# MSP430G2553_H-Bridge_Servo_Sensors_Inter.net
KiCad netlist of a schematic drawn in EAGLE
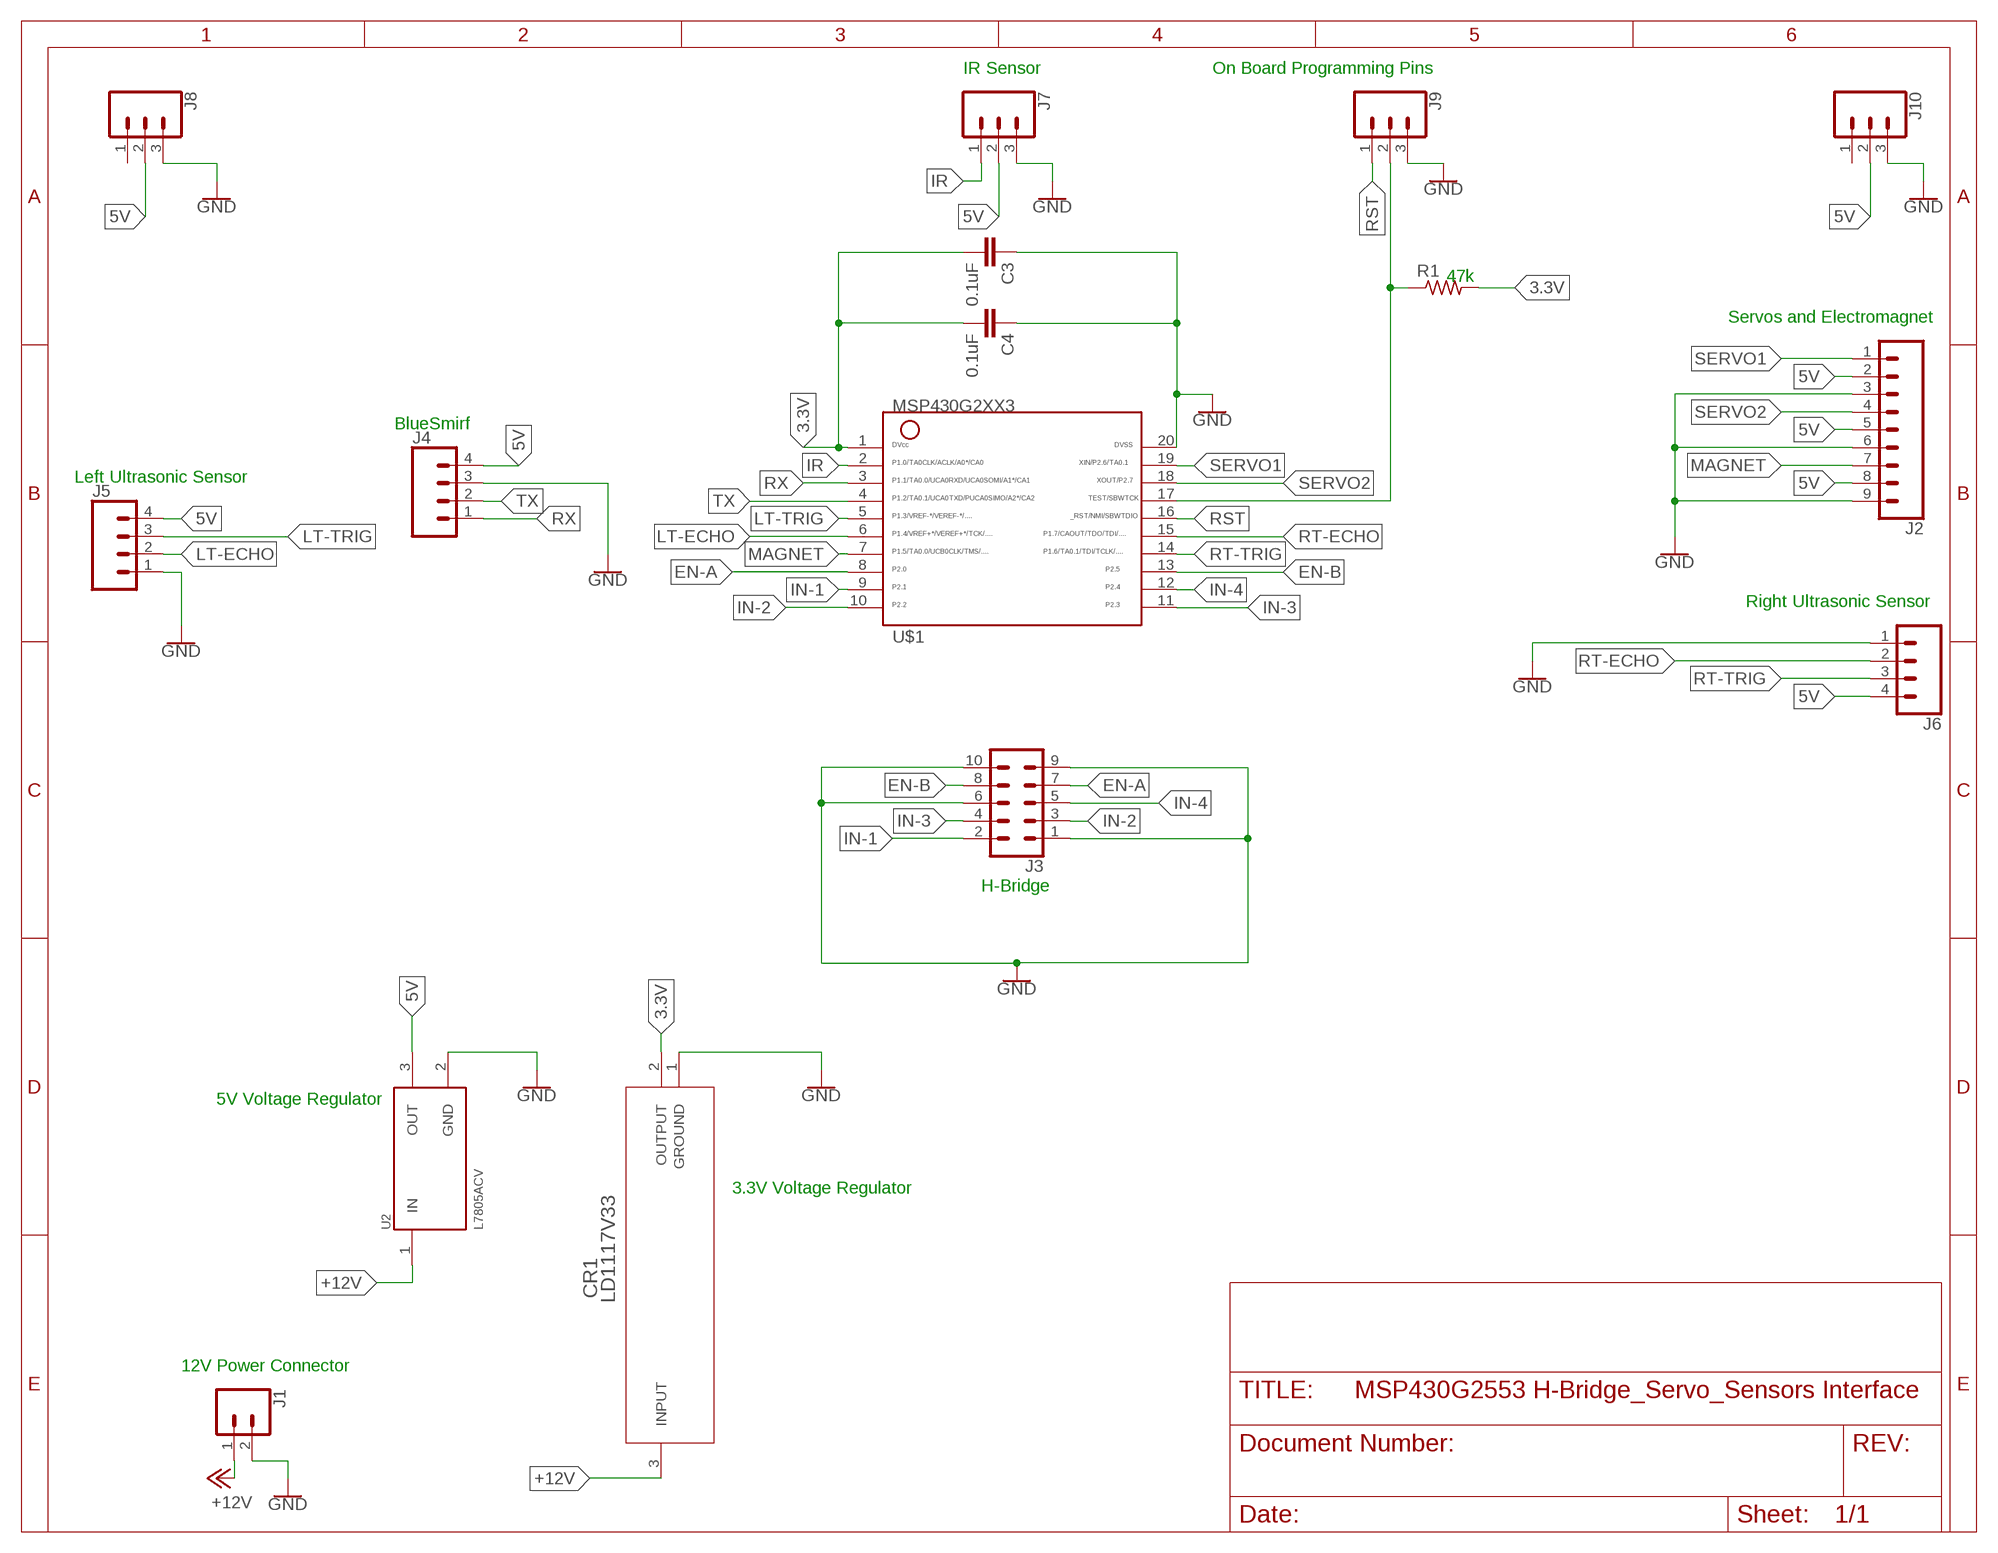
[diagram p0: schematic, sheet 1]

(export (version "E")
  (design (tool "Eeschema 10.0.6"))
  (components
    (comp (ref "C3")
      (value "0.1uF")
      (footprint "eagle-import:0402")
      (libsource (lib "eagle-import") (part "0.1UF-0402-16V-10%"))
    )
    (comp (ref "C4")
      (value "0.1uF")
      (footprint "eagle-import:0402")
      (libsource (lib "eagle-import") (part "0.1UF-0402-16V-10%"))
    )
    (comp (ref "CR1")
      (value "LD1117V33")
      (footprint "eagle-import:TO-220")
      (libsource (lib "eagle-import") (part "LD1117V33"))
    )
    (comp (ref "J1")
      (value "CONN_023.5MM")
      (footprint "eagle-import:SCREWTERMINAL-3.5MM-2")
      (libsource (lib "eagle-import") (part "CONN_023.5MM"))
    )
    (comp (ref "J2")
      (value "CONN_09")
      (footprint "eagle-import:1X09")
      (libsource (lib "eagle-import") (part "CONN_09"))
    )
    (comp (ref "J3")
      (value "CONN_05X2PTH")
      (footprint "eagle-import:2X5")
      (libsource (lib "eagle-import") (part "CONN_05X2PTH"))
    )
    (comp (ref "J4")
      (value "CONN_04")
      (footprint "eagle-import:1X04")
      (libsource (lib "eagle-import") (part "CONN_04"))
    )
    (comp (ref "J5")
      (value "CONN_04")
      (footprint "eagle-import:1X04")
      (libsource (lib "eagle-import") (part "CONN_04"))
    )
    (comp (ref "J6")
      (value "CONN_04")
      (footprint "eagle-import:1X04")
      (libsource (lib "eagle-import") (part "CONN_04"))
    )
    (comp (ref "J7")
      (value "CONN_03")
      (footprint "eagle-import:1X03")
      (libsource (lib "eagle-import") (part "CONN_03"))
    )
    (comp (ref "J8")
      (value "CONN_03")
      (footprint "eagle-import:1X03")
      (libsource (lib "eagle-import") (part "CONN_03"))
    )
    (comp (ref "J9")
      (value "CONN_03")
      (footprint "eagle-import:1X03")
      (libsource (lib "eagle-import") (part "CONN_03"))
    )
    (comp (ref "J10")
      (value "CONN_03")
      (footprint "eagle-import:1X03")
      (libsource (lib "eagle-import") (part "CONN_03"))
    )
    (comp (ref "R1")
      (value "R-US_R0201")
      (footprint "eagle-import:R0201")
      (libsource (lib "eagle-import") (part "R-US_R0201"))
    )
    (comp (ref "U$1")
      (value "G2XX3---N20")
      (footprint "eagle-import:N20")
      (libsource (lib "eagle-import") (part "G2XX3---N20"))
    )
    (comp (ref "U2")
      (value "L7805ACV")
      (footprint "eagle-import:TO254P460X1020X1945-3P")
      (fields (field (name "DIGI-KEY_PART_NUMBER") "497-1441-5-ND") (field (name "MF") "STMicroelectronics"))
      (libsource (lib "eagle-import") (part "L7805ACV"))
    )
  )
  (nets
    (net (code "1") (name "+12V") (class "Default")
      (node (ref "CR1") (pin "3") (pinfunction "INPUT_3") (pintype "passive"))
      (node (ref "J1") (pin "1") (pinfunction "1_1") (pintype "passive"))
      (node (ref "U2") (pin "1") (pinfunction "IN_1") (pintype "input"))
    )
    (net (code "2") (name "3.3V") (class "Default")
      (node (ref "C3") (pin "2") (pinfunction "2_2") (pintype "passive"))
      (node (ref "C4") (pin "2") (pinfunction "2_2") (pintype "passive"))
      (node (ref "CR1") (pin "2") (pinfunction "OUTPUT_2") (pintype "passive"))
      (node (ref "R1") (pin "2") (pinfunction "2_2") (pintype "passive"))
      (node (ref "U$1") (pin "1") (pinfunction "1_1") (pintype "bidirectional"))
    )
    (net (code "3") (name "5V") (class "Default")
      (node (ref "J10") (pin "2") (pinfunction "2_2") (pintype "passive"))
      (node (ref "J2") (pin "2") (pinfunction "2_2") (pintype "passive"))
      (node (ref "J2") (pin "5") (pinfunction "5_5") (pintype "passive"))
      (node (ref "J2") (pin "8") (pinfunction "8_8") (pintype "passive"))
      (node (ref "J4") (pin "4") (pinfunction "4_4") (pintype "passive"))
      (node (ref "J5") (pin "4") (pinfunction "4_4") (pintype "passive"))
      (node (ref "J6") (pin "4") (pinfunction "4_4") (pintype "passive"))
      (node (ref "J7") (pin "2") (pinfunction "2_2") (pintype "passive"))
      (node (ref "J8") (pin "2") (pinfunction "2_2") (pintype "passive"))
      (node (ref "U2") (pin "3") (pinfunction "OUT_3") (pintype "output"))
    )
    (net (code "4") (name "EN-A") (class "Default")
      (node (ref "J3") (pin "7") (pinfunction "7_7") (pintype "passive"))
      (node (ref "U$1") (pin "8") (pinfunction "8_8") (pintype "bidirectional"))
    )
    (net (code "5") (name "EN-B") (class "Default")
      (node (ref "J3") (pin "8") (pinfunction "8_8") (pintype "passive"))
      (node (ref "U$1") (pin "13") (pinfunction "13_13") (pintype "bidirectional"))
    )
    (net (code "6") (name "GND") (class "Default")
      (node (ref "C3") (pin "1") (pinfunction "1_1") (pintype "passive"))
      (node (ref "C4") (pin "1") (pinfunction "1_1") (pintype "passive"))
      (node (ref "CR1") (pin "1") (pinfunction "GROUND_1") (pintype "passive"))
      (node (ref "J1") (pin "2") (pinfunction "2_2") (pintype "passive"))
      (node (ref "J10") (pin "3") (pinfunction "3_3") (pintype "passive"))
      (node (ref "J2") (pin "3") (pinfunction "3_3") (pintype "passive"))
      (node (ref "J2") (pin "6") (pinfunction "6_6") (pintype "passive"))
      (node (ref "J2") (pin "9") (pinfunction "9_9") (pintype "passive"))
      (node (ref "J3") (pin "1") (pinfunction "1_1") (pintype "passive"))
      (node (ref "J3") (pin "10") (pinfunction "10_10") (pintype "passive"))
      (node (ref "J3") (pin "6") (pinfunction "6_6") (pintype "passive"))
      (node (ref "J3") (pin "9") (pinfunction "9_9") (pintype "passive"))
      (node (ref "J4") (pin "3") (pinfunction "3_3") (pintype "passive"))
      (node (ref "J5") (pin "1") (pinfunction "1_1") (pintype "passive"))
      (node (ref "J6") (pin "1") (pinfunction "1_1") (pintype "passive"))
      (node (ref "J7") (pin "3") (pinfunction "3_3") (pintype "passive"))
      (node (ref "J8") (pin "3") (pinfunction "3_3") (pintype "passive"))
      (node (ref "J9") (pin "3") (pinfunction "3_3") (pintype "passive"))
      (node (ref "U$1") (pin "20") (pinfunction "20_20") (pintype "bidirectional"))
      (node (ref "U2") (pin "2") (pinfunction "GND_2") (pintype "power_in"))
    )
    (net (code "7") (name "IN-1") (class "Default")
      (node (ref "J3") (pin "2") (pinfunction "2_2") (pintype "passive"))
      (node (ref "U$1") (pin "9") (pinfunction "9_9") (pintype "bidirectional"))
    )
    (net (code "8") (name "IN-2") (class "Default")
      (node (ref "J3") (pin "3") (pinfunction "3_3") (pintype "passive"))
      (node (ref "U$1") (pin "10") (pinfunction "10_10") (pintype "bidirectional"))
    )
    (net (code "9") (name "IN-3") (class "Default")
      (node (ref "J3") (pin "4") (pinfunction "4_4") (pintype "passive"))
      (node (ref "U$1") (pin "11") (pinfunction "11_11") (pintype "bidirectional"))
    )
    (net (code "10") (name "IN-4") (class "Default")
      (node (ref "J3") (pin "5") (pinfunction "5_5") (pintype "passive"))
      (node (ref "U$1") (pin "12") (pinfunction "12_12") (pintype "bidirectional"))
    )
    (net (code "11") (name "IR") (class "Default")
      (node (ref "J7") (pin "1") (pinfunction "1_1") (pintype "passive"))
      (node (ref "U$1") (pin "2") (pinfunction "2_2") (pintype "bidirectional"))
    )
    (net (code "12") (name "LT-ECHO") (class "Default")
      (node (ref "J5") (pin "2") (pinfunction "2_2") (pintype "passive"))
      (node (ref "U$1") (pin "6") (pinfunction "6_6") (pintype "bidirectional"))
    )
    (net (code "13") (name "LT-TRIG") (class "Default")
      (node (ref "J5") (pin "3") (pinfunction "3_3") (pintype "passive"))
      (node (ref "U$1") (pin "5") (pinfunction "5_5") (pintype "bidirectional"))
    )
    (net (code "14") (name "MAGNET") (class "Default")
      (node (ref "J2") (pin "7") (pinfunction "7_7") (pintype "passive"))
      (node (ref "U$1") (pin "7") (pinfunction "7_7") (pintype "bidirectional"))
    )
    (net (code "15") (name "Net-(J9-Pad2)") (class "Default")
      (node (ref "J9") (pin "2") (pinfunction "2_2") (pintype "passive"))
      (node (ref "R1") (pin "1") (pinfunction "1_1") (pintype "passive"))
      (node (ref "U$1") (pin "17") (pinfunction "17_17") (pintype "bidirectional"))
    )
    (net (code "16") (name "RST") (class "Default")
      (node (ref "J9") (pin "1") (pinfunction "1_1") (pintype "passive"))
      (node (ref "U$1") (pin "16") (pinfunction "16_16") (pintype "bidirectional"))
    )
    (net (code "17") (name "RT-ECHO") (class "Default")
      (node (ref "J6") (pin "2") (pinfunction "2_2") (pintype "passive"))
      (node (ref "U$1") (pin "15") (pinfunction "15_15") (pintype "bidirectional"))
    )
    (net (code "18") (name "RT-TRIG") (class "Default")
      (node (ref "J6") (pin "3") (pinfunction "3_3") (pintype "passive"))
      (node (ref "U$1") (pin "14") (pinfunction "14_14") (pintype "bidirectional"))
    )
    (net (code "19") (name "RX") (class "Default")
      (node (ref "J4") (pin "1") (pinfunction "1_1") (pintype "passive"))
      (node (ref "U$1") (pin "3") (pinfunction "3_3") (pintype "bidirectional"))
    )
    (net (code "20") (name "SERVO1") (class "Default")
      (node (ref "J2") (pin "1") (pinfunction "1_1") (pintype "passive"))
      (node (ref "U$1") (pin "19") (pinfunction "19_19") (pintype "bidirectional"))
    )
    (net (code "21") (name "SERVO2") (class "Default")
      (node (ref "J2") (pin "4") (pinfunction "4_4") (pintype "passive"))
      (node (ref "U$1") (pin "18") (pinfunction "18_18") (pintype "bidirectional"))
    )
    (net (code "22") (name "TX") (class "Default")
      (node (ref "J4") (pin "2") (pinfunction "2_2") (pintype "passive"))
      (node (ref "U$1") (pin "4") (pinfunction "4_4") (pintype "bidirectional"))
    )
    (net (code "23") (name "unconnected-(J8-Pad1)") (class "Default")
      (node (ref "J8") (pin "1") (pinfunction "1_1") (pintype "passive"))
    )
    (net (code "24") (name "unconnected-(J10-Pad1)") (class "Default")
      (node (ref "J10") (pin "1") (pinfunction "1_1") (pintype "passive"))
    )
  )
)
